# DrumMachine_Pic32_v1_2.net
KiCad netlist of a schematic drawn in EAGLE
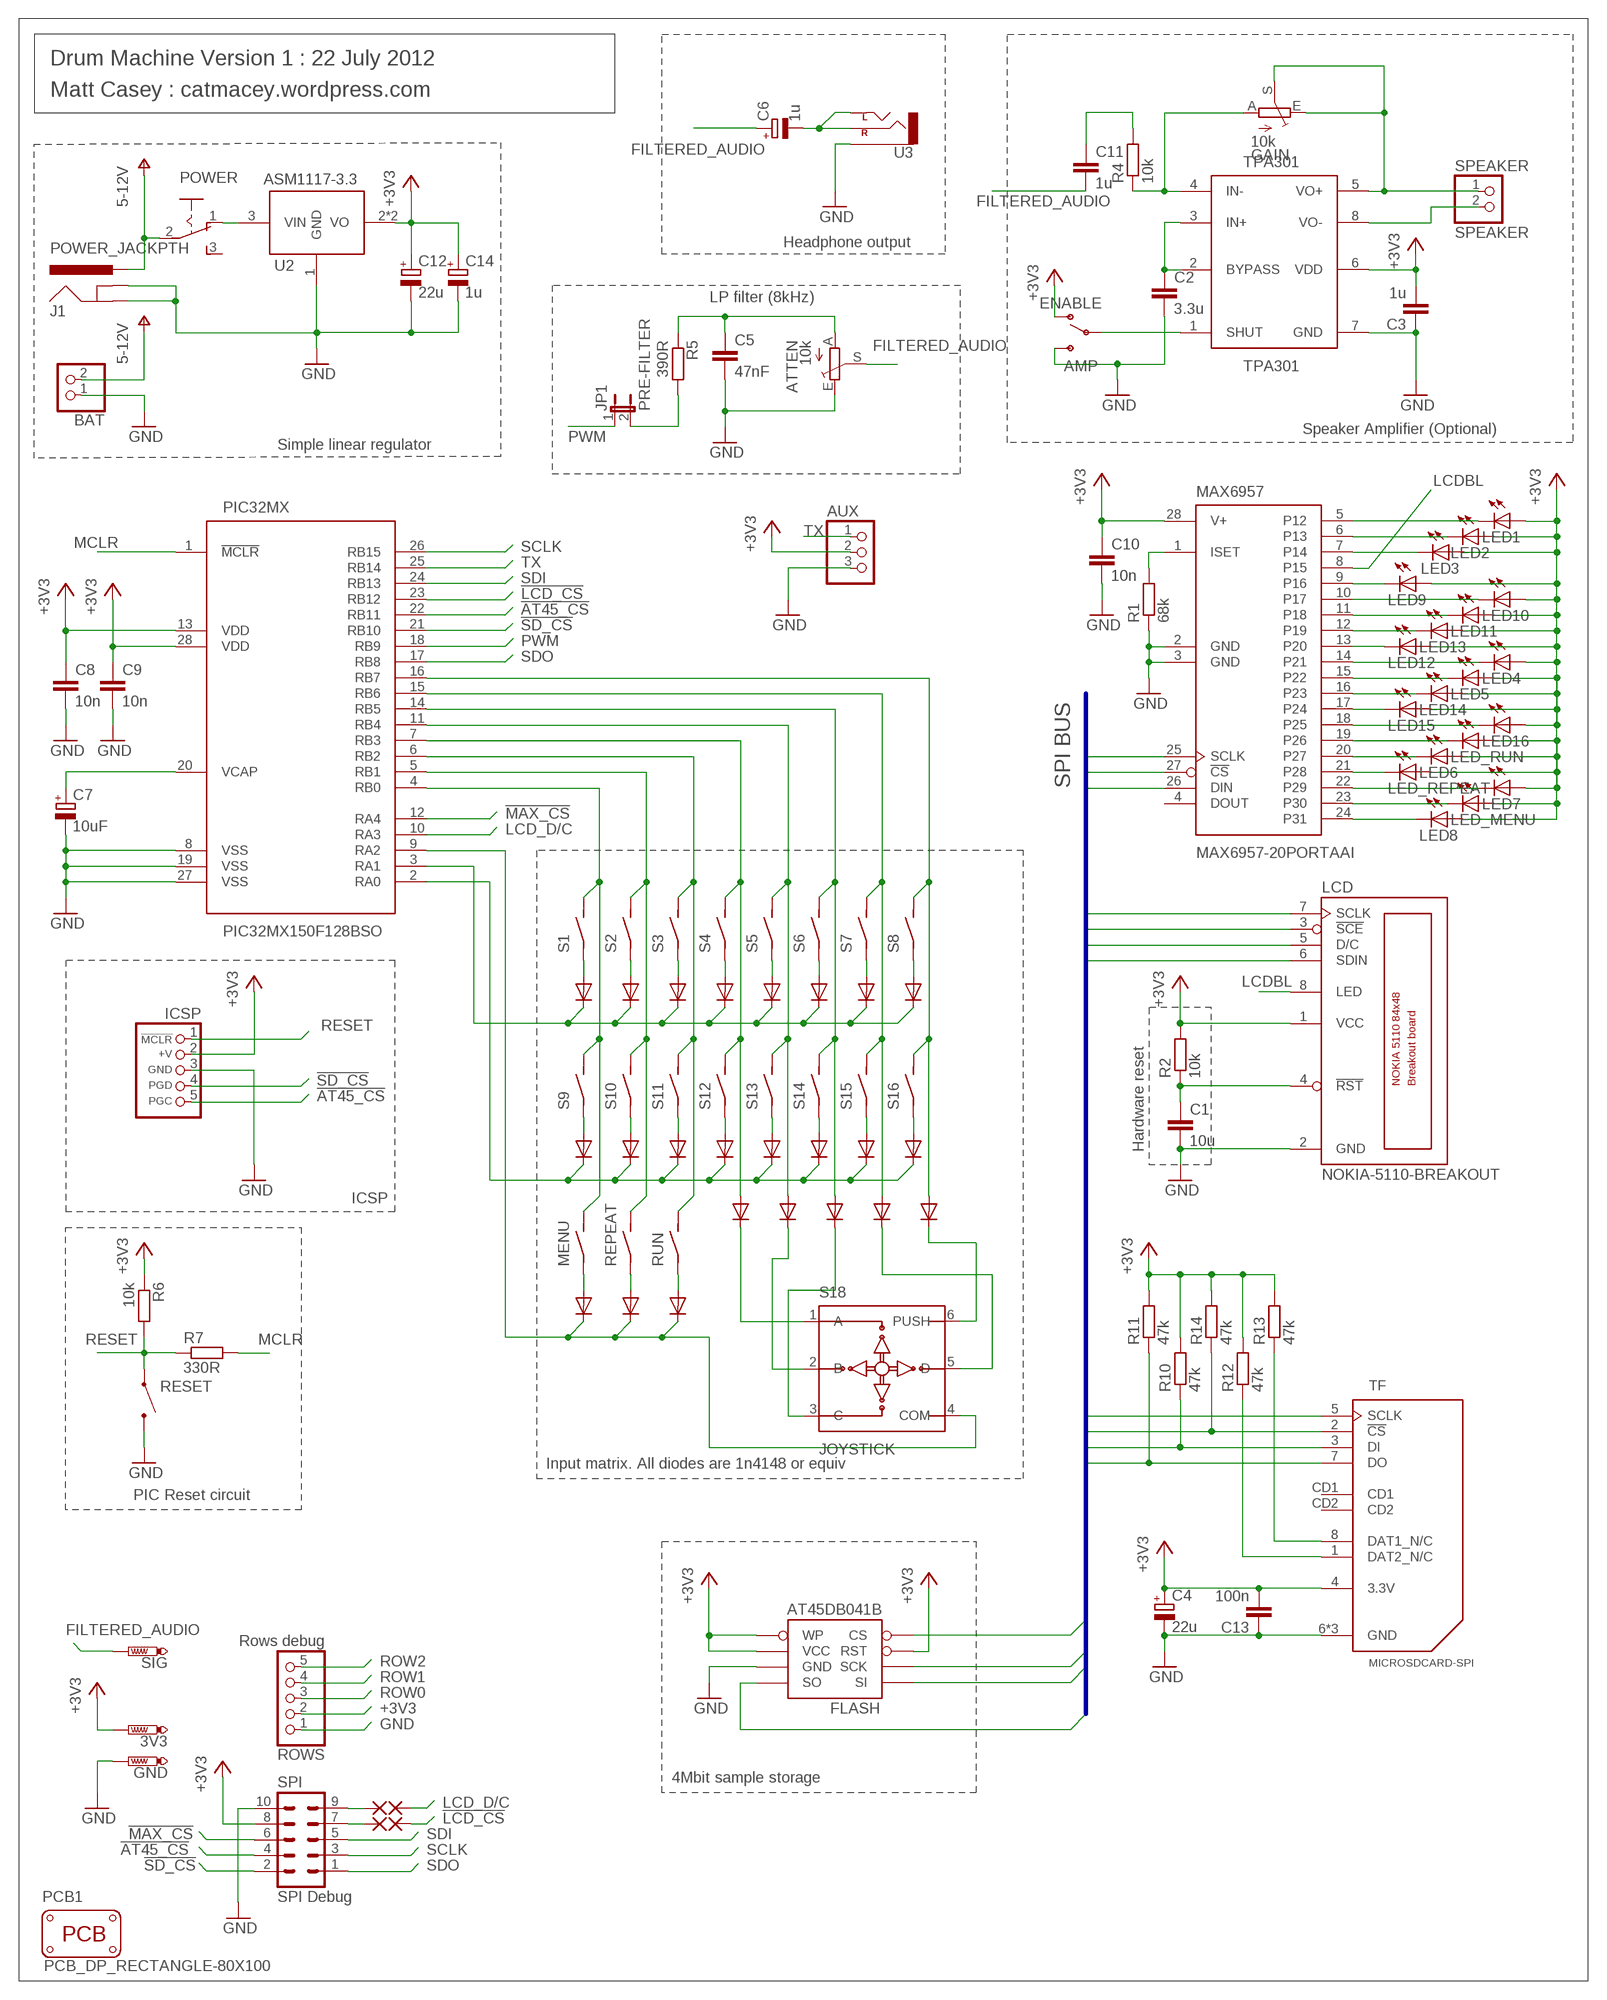
[diagram p0: schematic, sheet 1]

(export (version "E")
  (design (tool "Eeschema 10.0.6"))
  (components
    (comp (ref "3V3")
      (value "PTR1PAD1-13")
      (footprint "eagle-import:P1-13")
      (libsource (lib "eagle-import") (part "PTR1PAD1-13"))
    )
    (comp (ref "AMP")
      (value "ENABLE")
      (footprint "eagle-import:SWITCH-SPST-SMD-A")
      (libsource (lib "eagle-import") (part "SWITCH-SPST-SMD-A"))
    )
    (comp (ref "ATTEN")
      (value "10k")
      (footprint "eagle-import:CA6V")
      (libsource (lib "eagle-import") (part "TRIM_EU-CA6V"))
    )
    (comp (ref "AUX")
      (value "PINHD-1X3")
      (footprint "eagle-import:1X03")
      (libsource (lib "eagle-import") (part "PINHD-1X3"))
    )
    (comp (ref "BAT")
      (value "PINHD-1X2")
      (footprint "eagle-import:1X02")
      (libsource (lib "eagle-import") (part "PINHD-1X2"))
    )
    (comp (ref "C1")
      (value "10u")
      (footprint "eagle-import:C0805")
      (libsource (lib "eagle-import") (part "C-EUC0805"))
    )
    (comp (ref "C2")
      (value "3.3u")
      (footprint "eagle-import:C0805")
      (libsource (lib "eagle-import") (part "C-EUC0805"))
    )
    (comp (ref "C3")
      (value "1u")
      (footprint "eagle-import:C0805")
      (libsource (lib "eagle-import") (part "C-EUC0805"))
    )
    (comp (ref "C4")
      (value "22u")
      (footprint "eagle-import:SMC_A")
      (libsource (lib "eagle-import") (part "CPOL-EUSMCA"))
    )
    (comp (ref "C5")
      (value "47nF")
      (footprint "eagle-import:C0805")
      (libsource (lib "eagle-import") (part "C-EUC0805"))
    )
    (comp (ref "C6")
      (value "1u")
      (footprint "eagle-import:153CLV-0405")
      (libsource (lib "eagle-import") (part "CPOL-EU153CLV-0405"))
    )
    (comp (ref "C7")
      (value "10uF")
      (footprint "eagle-import:SMC_A")
      (libsource (lib "eagle-import") (part "CPOL-EUSMCA"))
    )
    (comp (ref "C8")
      (value "10n")
      (footprint "eagle-import:C0805")
      (libsource (lib "eagle-import") (part "resistor_C-EUC0805"))
    )
    (comp (ref "C9")
      (value "10n")
      (footprint "eagle-import:C0805")
      (libsource (lib "eagle-import") (part "resistor_C-EUC0805"))
    )
    (comp (ref "C10")
      (value "10n")
      (footprint "eagle-import:C0805")
      (libsource (lib "eagle-import") (part "resistor_C-EUC0805"))
    )
    (comp (ref "C11")
      (value "1u")
      (footprint "eagle-import:C0805")
      (libsource (lib "eagle-import") (part "C-EUC0805"))
    )
    (comp (ref "C12")
      (value "22u")
      (footprint "eagle-import:SMC_A")
      (libsource (lib "eagle-import") (part "CPOL-EUSMCA"))
    )
    (comp (ref "C13")
      (value "100n")
      (footprint "eagle-import:C0805")
      (libsource (lib "eagle-import") (part "resistor_C-EUC0805"))
    )
    (comp (ref "C14")
      (value "1u")
      (footprint "eagle-import:153CLV-0405")
      (libsource (lib "eagle-import") (part "CPOL-EU153CLV-0405"))
    )
    (comp (ref "D1")
      (value "DIODE-SOD-123")
      (footprint "eagle-import:SOD-123")
      (libsource (lib "eagle-import") (part "DIODE-SOD-123"))
    )
    (comp (ref "D2")
      (value "DIODE-SOD-123")
      (footprint "eagle-import:SOD-123")
      (libsource (lib "eagle-import") (part "DIODE-SOD-123"))
    )
    (comp (ref "D3")
      (value "DIODE-SOD-123")
      (footprint "eagle-import:SOD-123")
      (libsource (lib "eagle-import") (part "DIODE-SOD-123"))
    )
    (comp (ref "D4")
      (value "DIODE-SOD-123")
      (footprint "eagle-import:SOD-123")
      (libsource (lib "eagle-import") (part "DIODE-SOD-123"))
    )
    (comp (ref "D5")
      (value "DIODE-SOD-123")
      (footprint "eagle-import:SOD-123")
      (libsource (lib "eagle-import") (part "DIODE-SOD-123"))
    )
    (comp (ref "D6")
      (value "DIODE-SOD-123")
      (footprint "eagle-import:SOD-123")
      (libsource (lib "eagle-import") (part "DIODE-SOD-123"))
    )
    (comp (ref "D7")
      (value "DIODE-SOD-123")
      (footprint "eagle-import:SOD-123")
      (libsource (lib "eagle-import") (part "DIODE-SOD-123"))
    )
    (comp (ref "D8")
      (value "DIODE-SOD-123")
      (footprint "eagle-import:SOD-123")
      (libsource (lib "eagle-import") (part "DIODE-SOD-123"))
    )
    (comp (ref "D9")
      (value "DIODE-SOD-123")
      (footprint "eagle-import:SOD-123")
      (libsource (lib "eagle-import") (part "DIODE-SOD-123"))
    )
    (comp (ref "D10")
      (value "DIODE-SOD-123")
      (footprint "eagle-import:SOD-123")
      (libsource (lib "eagle-import") (part "DIODE-SOD-123"))
    )
    (comp (ref "D11")
      (value "DIODE-SOD-123")
      (footprint "eagle-import:SOD-123")
      (libsource (lib "eagle-import") (part "DIODE-SOD-123"))
    )
    (comp (ref "D12")
      (value "DIODE-SOD-123")
      (footprint "eagle-import:SOD-123")
      (libsource (lib "eagle-import") (part "DIODE-SOD-123"))
    )
    (comp (ref "D13")
      (value "DIODE-SOD-123")
      (footprint "eagle-import:SOD-123")
      (libsource (lib "eagle-import") (part "DIODE-SOD-123"))
    )
    (comp (ref "D14")
      (value "DIODE-SOD-123")
      (footprint "eagle-import:SOD-123")
      (libsource (lib "eagle-import") (part "DIODE-SOD-123"))
    )
    (comp (ref "D15")
      (value "DIODE-SOD-123")
      (footprint "eagle-import:SOD-123")
      (libsource (lib "eagle-import") (part "DIODE-SOD-123"))
    )
    (comp (ref "D16")
      (value "DIODE-SOD-123")
      (footprint "eagle-import:SOD-123")
      (libsource (lib "eagle-import") (part "DIODE-SOD-123"))
    )
    (comp (ref "D17")
      (value "DIODE-SOD-123")
      (footprint "eagle-import:SOD-123")
      (libsource (lib "eagle-import") (part "DIODE-SOD-123"))
    )
    (comp (ref "D18")
      (value "DIODE-SOD-123")
      (footprint "eagle-import:SOD-123")
      (libsource (lib "eagle-import") (part "DIODE-SOD-123"))
    )
    (comp (ref "D19")
      (value "DIODE-SOD-123")
      (footprint "eagle-import:SOD-123")
      (libsource (lib "eagle-import") (part "DIODE-SOD-123"))
    )
    (comp (ref "D20")
      (value "DIODE-SOD-123")
      (footprint "eagle-import:SOD-123")
      (libsource (lib "eagle-import") (part "DIODE-SOD-123"))
    )
    (comp (ref "D21")
      (value "DIODE-SOD-123")
      (footprint "eagle-import:SOD-123")
      (libsource (lib "eagle-import") (part "DIODE-SOD-123"))
    )
    (comp (ref "D22")
      (value "DIODE-SOD-123")
      (footprint "eagle-import:SOD-123")
      (libsource (lib "eagle-import") (part "DIODE-SOD-123"))
    )
    (comp (ref "D23")
      (value "DIODE-SOD-123")
      (footprint "eagle-import:SOD-123")
      (libsource (lib "eagle-import") (part "DIODE-SOD-123"))
    )
    (comp (ref "D25")
      (value "DIODE-SOD-123")
      (footprint "eagle-import:SOD-123")
      (libsource (lib "eagle-import") (part "DIODE-SOD-123"))
    )
    (comp (ref "FLASH")
      (value "AT45DB041B")
      (footprint "eagle-import:SO08")
      (libsource (lib "eagle-import") (part "AT45DB041B"))
    )
    (comp (ref "GAIN")
      (value "10k")
      (footprint "eagle-import:CA6V")
      (libsource (lib "eagle-import") (part "TRIM_EU-CA6V"))
    )
    (comp (ref "GND")
      (value "PTR1PAD1-13")
      (footprint "eagle-import:P1-13")
      (libsource (lib "eagle-import") (part "PTR1PAD1-13"))
    )
    (comp (ref "ICSP")
      (value "CON_HEADER_PRG_PIC_ICSPB")
      (footprint "eagle-import:HEADER_PRG_1X05_ICSP_B")
      (libsource (lib "eagle-import") (part "CON_HEADER_PRG_PIC_ICSPB"))
    )
    (comp (ref "J1")
      (value "POWER_JACKPTH")
      (footprint "eagle-import:POWER_JACK_PTH")
      (libsource (lib "eagle-import") (part "POWER_JACKPTH"))
    )
    (comp (ref "JP1")
      (value "PRE-FILTER")
      (footprint "eagle-import:JP1")
      (libsource (lib "eagle-import") (part "JP1E"))
    )
    (comp (ref "LCD")
      (value "NOKIA-5110-BREAKOUT")
      (footprint "eagle-import:NOKIA-5110-BREAKOUT")
      (libsource (lib "eagle-import") (part "NOKIA-5110-BREAKOUT"))
    )
    (comp (ref "LED1")
      (value "LEDCHIPLED_0805")
      (footprint "eagle-import:CHIPLED_0805")
      (libsource (lib "eagle-import") (part "LEDCHIPLED_0805"))
    )
    (comp (ref "LED2")
      (value "LEDCHIPLED_0805")
      (footprint "eagle-import:CHIPLED_0805")
      (libsource (lib "eagle-import") (part "LEDCHIPLED_0805"))
    )
    (comp (ref "LED3")
      (value "LEDCHIPLED_0805")
      (footprint "eagle-import:CHIPLED_0805")
      (libsource (lib "eagle-import") (part "LEDCHIPLED_0805"))
    )
    (comp (ref "LED4")
      (value "LEDCHIPLED_0805")
      (footprint "eagle-import:CHIPLED_0805")
      (libsource (lib "eagle-import") (part "LEDCHIPLED_0805"))
    )
    (comp (ref "LED5")
      (value "LEDCHIPLED_0805")
      (footprint "eagle-import:CHIPLED_0805")
      (libsource (lib "eagle-import") (part "LEDCHIPLED_0805"))
    )
    (comp (ref "LED6")
      (value "LEDCHIPLED_0805")
      (footprint "eagle-import:CHIPLED_0805")
      (libsource (lib "eagle-import") (part "LEDCHIPLED_0805"))
    )
    (comp (ref "LED7")
      (value "LEDCHIPLED_0805")
      (footprint "eagle-import:CHIPLED_0805")
      (libsource (lib "eagle-import") (part "LEDCHIPLED_0805"))
    )
    (comp (ref "LED8")
      (value "LEDCHIPLED_0805")
      (footprint "eagle-import:CHIPLED_0805")
      (libsource (lib "eagle-import") (part "LEDCHIPLED_0805"))
    )
    (comp (ref "LED9")
      (value "LEDCHIPLED_0805")
      (footprint "eagle-import:CHIPLED_0805")
      (libsource (lib "eagle-import") (part "LEDCHIPLED_0805"))
    )
    (comp (ref "LED10")
      (value "LEDCHIPLED_0805")
      (footprint "eagle-import:CHIPLED_0805")
      (libsource (lib "eagle-import") (part "LEDCHIPLED_0805"))
    )
    (comp (ref "LED11")
      (value "LEDCHIPLED_0805")
      (footprint "eagle-import:CHIPLED_0805")
      (libsource (lib "eagle-import") (part "LEDCHIPLED_0805"))
    )
    (comp (ref "LED12")
      (value "LEDCHIPLED_0805")
      (footprint "eagle-import:CHIPLED_0805")
      (libsource (lib "eagle-import") (part "LEDCHIPLED_0805"))
    )
    (comp (ref "LED13")
      (value "LEDCHIPLED_0805")
      (footprint "eagle-import:CHIPLED_0805")
      (libsource (lib "eagle-import") (part "LEDCHIPLED_0805"))
    )
    (comp (ref "LED14")
      (value "LEDCHIPLED_0805")
      (footprint "eagle-import:CHIPLED_0805")
      (libsource (lib "eagle-import") (part "LEDCHIPLED_0805"))
    )
    (comp (ref "LED15")
      (value "LEDCHIPLED_0805")
      (footprint "eagle-import:CHIPLED_0805")
      (libsource (lib "eagle-import") (part "LEDCHIPLED_0805"))
    )
    (comp (ref "LED16")
      (value "LEDCHIPLED_0805")
      (footprint "eagle-import:CHIPLED_0805")
      (libsource (lib "eagle-import") (part "LEDCHIPLED_0805"))
    )
    (comp (ref "LED_MENU")
      (value "LEDCHIPLED_0805")
      (footprint "eagle-import:CHIPLED_0805")
      (libsource (lib "eagle-import") (part "LEDCHIPLED_0805"))
    )
    (comp (ref "LED_REPEAT")
      (value "LEDCHIPLED_0805")
      (footprint "eagle-import:CHIPLED_0805")
      (libsource (lib "eagle-import") (part "LEDCHIPLED_0805"))
    )
    (comp (ref "LED_RUN")
      (value "LEDCHIPLED_0805")
      (footprint "eagle-import:CHIPLED_0805")
      (libsource (lib "eagle-import") (part "LEDCHIPLED_0805"))
    )
    (comp (ref "MAX6957")
      (value "MAX6957-20PORTAAI")
      (footprint "eagle-import:SSOP28")
      (libsource (lib "eagle-import") (part "MAX6957-20PORTAAI"))
    )
    (comp (ref "MENU")
      (value "ITT-PTS645SMD")
      (footprint "eagle-import:ITT-PTS645SMD")
      (libsource (lib "eagle-import") (part "ITT-PTS645SMD"))
    )
    (comp (ref "P1")
      (value "DEBUG_LCD_CS")
      (footprint "eagle-import:1,2_0,5")
      (libsource (lib "eagle-import") (part "1,6/0,81.2/0.5"))
    )
    (comp (ref "P1A")
      (value "LCD CS")
      (footprint "eagle-import:1,2_0,5")
      (libsource (lib "eagle-import") (part "1,6/0,81.2/0.5"))
    )
    (comp (ref "P2")
      (value "DEBUG_LCD_D/c")
      (footprint "eagle-import:1,2_0,5")
      (libsource (lib "eagle-import") (part "1,6/0,81.2/0.5"))
    )
    (comp (ref "P2A")
      (value "1,6/0,81.2/0.5")
      (footprint "eagle-import:1,2_0,5")
      (libsource (lib "eagle-import") (part "1,6/0,81.2/0.5"))
    )
    (comp (ref "PCB1")
      (value "PCB_DP_RECTANGLE-80X100")
      (footprint "eagle-import:DP10080_V1")
      (libsource (lib "eagle-import") (part "PCB_DP_RECTANGLE-80X100"))
    )
    (comp (ref "PIC32MX")
      (value "PIC32MX150F128BSO")
      (footprint "eagle-import:SO-28")
      (libsource (lib "eagle-import") (part "PIC32MX150F128BSO"))
    )
    (comp (ref "POWER")
      (value "DX_MINI_SPDT")
      (footprint "eagle-import:DX_MINI_SPDT_VERTICAL")
      (libsource (lib "eagle-import") (part "DX_MINI_SPDT"))
    )
    (comp (ref "R1")
      (value "68k")
      (footprint "eagle-import:R0805")
      (libsource (lib "eagle-import") (part "R-EU_R0805"))
    )
    (comp (ref "R2")
      (value "10k")
      (footprint "eagle-import:R0805")
      (libsource (lib "eagle-import") (part "R-EU_R0805"))
    )
    (comp (ref "R4")
      (value "10k")
      (footprint "eagle-import:R0805")
      (libsource (lib "eagle-import") (part "R-EU_R0805"))
    )
    (comp (ref "R5")
      (value "390R")
      (footprint "eagle-import:R0805")
      (libsource (lib "eagle-import") (part "R-EU_R0805"))
    )
    (comp (ref "R6")
      (value "10k")
      (footprint "eagle-import:R0805")
      (libsource (lib "eagle-import") (part "R-EU_R0805"))
    )
    (comp (ref "R7")
      (value "330R")
      (footprint "eagle-import:R0805")
      (libsource (lib "eagle-import") (part "R-EU_R0805"))
    )
    (comp (ref "R10")
      (value "47k")
      (footprint "eagle-import:R0805")
      (libsource (lib "eagle-import") (part "R-EU_R0805"))
    )
    (comp (ref "R11")
      (value "47k")
      (footprint "eagle-import:R0805")
      (libsource (lib "eagle-import") (part "R-EU_R0805"))
    )
    (comp (ref "R12")
      (value "47k")
      (footprint "eagle-import:R0805")
      (libsource (lib "eagle-import") (part "R-EU_R0805"))
    )
    (comp (ref "R13")
      (value "47k")
      (footprint "eagle-import:R0805")
      (libsource (lib "eagle-import") (part "R-EU_R0805"))
    )
    (comp (ref "R14")
      (value "47k")
      (footprint "eagle-import:R0805")
      (libsource (lib "eagle-import") (part "R-EU_R0805"))
    )
    (comp (ref "REPEAT")
      (value "ITT-PTS645SMD")
      (footprint "eagle-import:ITT-PTS645SMD")
      (libsource (lib "eagle-import") (part "ITT-PTS645SMD"))
    )
    (comp (ref "RESET")
      (value "TINY_TACTILESMD")
      (footprint "eagle-import:TINY_TACTILE_SMD")
      (libsource (lib "eagle-import") (part "TINY_TACTILESMD"))
    )
    (comp (ref "ROWS")
      (value "Rows debug")
      (footprint "eagle-import:1X05")
      (libsource (lib "eagle-import") (part "PINHD-1X5"))
    )
    (comp (ref "RUN")
      (value "ITT-PTS645SMD")
      (footprint "eagle-import:ITT-PTS645SMD")
      (libsource (lib "eagle-import") (part "ITT-PTS645SMD"))
    )
    (comp (ref "S1")
      (value "ITT-PTS645SMD")
      (footprint "eagle-import:ITT-PTS645SMD")
      (libsource (lib "eagle-import") (part "ITT-PTS645SMD"))
    )
    (comp (ref "S2")
      (value "ITT-PTS645SMD")
      (footprint "eagle-import:ITT-PTS645SMD")
      (libsource (lib "eagle-import") (part "ITT-PTS645SMD"))
    )
    (comp (ref "S3")
      (value "ITT-PTS645SMD")
      (footprint "eagle-import:ITT-PTS645SMD")
      (libsource (lib "eagle-import") (part "ITT-PTS645SMD"))
    )
    (comp (ref "S4")
      (value "ITT-PTS645SMD")
      (footprint "eagle-import:ITT-PTS645SMD")
      (libsource (lib "eagle-import") (part "ITT-PTS645SMD"))
    )
    (comp (ref "S5")
      (value "ITT-PTS645SMD")
      (footprint "eagle-import:ITT-PTS645SMD")
      (libsource (lib "eagle-import") (part "ITT-PTS645SMD"))
    )
    (comp (ref "S6")
      (value "ITT-PTS645SMD")
      (footprint "eagle-import:ITT-PTS645SMD")
      (libsource (lib "eagle-import") (part "ITT-PTS645SMD"))
    )
    (comp (ref "S7")
      (value "ITT-PTS645SMD")
      (footprint "eagle-import:ITT-PTS645SMD")
      (libsource (lib "eagle-import") (part "ITT-PTS645SMD"))
    )
    (comp (ref "S8")
      (value "ITT-PTS645SMD")
      (footprint "eagle-import:ITT-PTS645SMD")
      (libsource (lib "eagle-import") (part "ITT-PTS645SMD"))
    )
    (comp (ref "S9")
      (value "ITT-PTS645SMD")
      (footprint "eagle-import:ITT-PTS645SMD")
      (libsource (lib "eagle-import") (part "ITT-PTS645SMD"))
    )
    (comp (ref "S10")
      (value "ITT-PTS645SMD")
      (footprint "eagle-import:ITT-PTS645SMD")
      (libsource (lib "eagle-import") (part "ITT-PTS645SMD"))
    )
    (comp (ref "S11")
      (value "ITT-PTS645SMD")
      (footprint "eagle-import:ITT-PTS645SMD")
      (libsource (lib "eagle-import") (part "ITT-PTS645SMD"))
    )
    (comp (ref "S12")
      (value "ITT-PTS645SMD")
      (footprint "eagle-import:ITT-PTS645SMD")
      (libsource (lib "eagle-import") (part "ITT-PTS645SMD"))
    )
    (comp (ref "S13")
      (value "ITT-PTS645SMD")
      (footprint "eagle-import:ITT-PTS645SMD")
      (libsource (lib "eagle-import") (part "ITT-PTS645SMD"))
    )
    (comp (ref "S14")
      (value "ITT-PTS645SMD")
      (footprint "eagle-import:ITT-PTS645SMD")
      (libsource (lib "eagle-import") (part "ITT-PTS645SMD"))
    )
    (comp (ref "S15")
      (value "ITT-PTS645SMD")
      (footprint "eagle-import:ITT-PTS645SMD")
      (libsource (lib "eagle-import") (part "ITT-PTS645SMD"))
    )
    (comp (ref "S16")
      (value "ITT-PTS645SMD")
      (footprint "eagle-import:ITT-PTS645SMD")
      (libsource (lib "eagle-import") (part "ITT-PTS645SMD"))
    )
    (comp (ref "S18")
      (value "JOYSTICK")
      (footprint "eagle-import:ALPS_SKQU_JOYSTICK")
      (libsource (lib "eagle-import") (part "ALPS_SKQU_JOYSTICK"))
    )
    (comp (ref "SIG")
      (value "PTR1PAD1-13")
      (footprint "eagle-import:P1-13")
      (libsource (lib "eagle-import") (part "PTR1PAD1-13"))
    )
    (comp (ref "SPEAKER")
      (value "SPEAKER")
      (footprint "eagle-import:1X02")
      (libsource (lib "eagle-import") (part "PINHD-1X2"))
    )
    (comp (ref "SPI")
      (value "SPI Debug")
      (footprint "eagle-import:MA05-2")
      (libsource (lib "eagle-import") (part "MA05-2"))
    )
    (comp (ref "TF")
      (value "MICROSDCARD-SPI")
      (footprint "eagle-import:TCF001_MICROSD_SOCKET")
      (libsource (lib "eagle-import") (part "MICROSDCARD-SPI"))
    )
    (comp (ref "TPA301")
      (value "TPA301")
      (footprint "eagle-import:SO-08")
      (libsource (lib "eagle-import") (part "TPA301"))
    )
    (comp (ref "U2")
      (value "ASM1117-3.3")
      (footprint "eagle-import:SOT223")
      (libsource (lib "eagle-import") (part "ASM1117-3.3"))
    )
    (comp (ref "U3")
      (value "AUDIO-JACKPTH")
      (footprint "eagle-import:STEREO_JACK3.5MM_PTH")
      (libsource (lib "eagle-import") (part "AUDIO-JACKPTH"))
    )
  )
  (nets
    (net (code "1") (name "+3V3") (class "Default")
      (node (ref "3V3") (pin "TP") (pinfunction "TP_TP") (pintype "input"))
      (node (ref "AMP") (pin "1") (pinfunction "O_1") (pintype "passive"))
      (node (ref "AUX") (pin "2") (pinfunction "2_2") (pintype "passive"))
      (node (ref "C10") (pin "1") (pinfunction "1_1") (pintype "passive"))
      (node (ref "C12") (pin "+") (pinfunction "+_+") (pintype "passive"))
      (node (ref "C13") (pin "2") (pinfunction "2_2") (pintype "passive"))
      (node (ref "C14") (pin "+") (pinfunction "+_+") (pintype "passive"))
      (node (ref "C3") (pin "2") (pinfunction "2_2") (pintype "passive"))
      (node (ref "C4") (pin "+") (pinfunction "+_+") (pintype "passive"))
      (node (ref "C8") (pin "1") (pinfunction "1_1") (pintype "passive"))
      (node (ref "C9") (pin "1") (pinfunction "1_1") (pintype "passive"))
      (node (ref "FLASH") (pin "3") (pinfunction "RST_3") (pintype "bidirectional"))
      (node (ref "FLASH") (pin "5") (pinfunction "WP_5") (pintype "bidirectional"))
      (node (ref "FLASH") (pin "6") (pinfunction "VCC_6") (pintype "bidirectional"))
      (node (ref "ICSP") (pin "2") (pinfunction "+V_2") (pintype "passive"))
      (node (ref "LCD") (pin "1") (pinfunction "VCC_1") (pintype "power_in"))
      (node (ref "LED1") (pin "A") (pinfunction "A_A") (pintype "passive"))
      (node (ref "LED10") (pin "A") (pinfunction "A_A") (pintype "passive"))
      (node (ref "LED11") (pin "A") (pinfunction "A_A") (pintype "passive"))
      (node (ref "LED12") (pin "A") (pinfunction "A_A") (pintype "passive"))
      (node (ref "LED13") (pin "A") (pinfunction "A_A") (pintype "passive"))
      (node (ref "LED14") (pin "A") (pinfunction "A_A") (pintype "passive"))
      (node (ref "LED15") (pin "A") (pinfunction "A_A") (pintype "passive"))
      (node (ref "LED16") (pin "A") (pinfunction "A_A") (pintype "passive"))
      (node (ref "LED2") (pin "A") (pinfunction "A_A") (pintype "passive"))
      (node (ref "LED3") (pin "A") (pinfunction "A_A") (pintype "passive"))
      (node (ref "LED4") (pin "A") (pinfunction "A_A") (pintype "passive"))
      (node (ref "LED5") (pin "A") (pinfunction "A_A") (pintype "passive"))
      (node (ref "LED6") (pin "A") (pinfunction "A_A") (pintype "passive"))
      (node (ref "LED7") (pin "A") (pinfunction "A_A") (pintype "passive"))
      (node (ref "LED8") (pin "A") (pinfunction "A_A") (pintype "passive"))
      (node (ref "LED9") (pin "A") (pinfunction "A_A") (pintype "passive"))
      (node (ref "LED_MENU") (pin "A") (pinfunction "A_A") (pintype "passive"))
      (node (ref "LED_REPEAT") (pin "A") (pinfunction "A_A") (pintype "passive"))
      (node (ref "LED_RUN") (pin "A") (pinfunction "A_A") (pintype "passive"))
      (node (ref "MAX6957") (pin "28") (pinfunction "V+_28") (pintype "power_in"))
      (node (ref "PIC32MX") (pin "13") (pinfunction "VDD_13") (pintype "power_in"))
      (node (ref "PIC32MX") (pin "28") (pinfunction "VDD_28") (pintype "power_in"))
      (node (ref "R10") (pin "2") (pinfunction "2_2") (pintype "passive"))
      (node (ref "R11") (pin "2") (pinfunction "2_2") (pintype "passive"))
      (node (ref "R12") (pin "2") (pinfunction "2_2") (pintype "passive"))
      (node (ref "R13") (pin "2") (pinfunction "2_2") (pintype "passive"))
      (node (ref "R14") (pin "2") (pinfunction "2_2") (pintype "passive"))
      (node (ref "R2") (pin "2") (pinfunction "2_2") (pintype "passive"))
      (node (ref "R6") (pin "1") (pinfunction "1_1") (pintype "passive"))
      (node (ref "ROWS") (pin "2") (pinfunction "2_2") (pintype "passive"))
      (node (ref "SPI") (pin "8") (pinfunction "8_8") (pintype "passive"))
      (node (ref "TF") (pin "4") (pinfunction "3.3V_4") (pintype "power_in"))
      (node (ref "TPA301") (pin "6") (pinfunction "VDD_6") (pintype "power_in"))
      (node (ref "U2") (pin "2") (pinfunction "VO_2") (pintype "bidirectional"))
      (node (ref "U2") (pin "4") (pinfunction "VO_4") (pintype "bidirectional"))
    )
    (net (code "2") (name "/FILTERED_AUDIO") (class "Default")
      (node (ref "ATTEN") (pin "S") (pinfunction "S_S") (pintype "passive"))
      (node (ref "C11") (pin "2") (pinfunction "2_2") (pintype "passive"))
      (node (ref "C6") (pin "+") (pinfunction "+_+") (pintype "passive"))
      (node (ref "SIG") (pin "TP") (pinfunction "TP_TP") (pintype "input"))
    )
    (net (code "3") (name "/LCDBL") (class "Default")
      (node (ref "LCD") (pin "8") (pinfunction "LED_8") (pintype "passive"))
      (node (ref "MAX6957") (pin "8") (pinfunction "P15_8") (pintype "bidirectional"))
    )
    (net (code "4") (name "/LCD_D{slash}C") (class "Default")
      (node (ref "LCD") (pin "5") (pinfunction "D/C_5") (pintype "input"))
      (node (ref "P2") (pin "1") (pinfunction "P_1") (pintype "passive"))
      (node (ref "P2A") (pin "1") (pinfunction "P_1") (pintype "passive"))
      (node (ref "PIC32MX") (pin "10") (pinfunction "RA3_10") (pintype "bidirectional"))
      (node (ref "SPI") (pin "9") (pinfunction "9_9") (pintype "passive"))
    )
    (net (code "5") (name "/MCLR") (class "Default")
      (node (ref "PIC32MX") (pin "1") (pinfunction "~{MCLR}_1") (pintype "input"))
      (node (ref "R7") (pin "2") (pinfunction "2_2") (pintype "passive"))
    )
    (net (code "6") (name "/PWM") (class "Default")
      (node (ref "JP1") (pin "1") (pinfunction "1_1") (pintype "passive"))
      (node (ref "PIC32MX") (pin "18") (pinfunction "RB9_18") (pintype "bidirectional"))
    )
    (net (code "7") (name "/RESET") (class "Default")
      (node (ref "ICSP") (pin "1") (pinfunction "/MCLR_1") (pintype "passive"))
      (node (ref "R6") (pin "2") (pinfunction "2_2") (pintype "passive"))
      (node (ref "R7") (pin "1") (pinfunction "1_1") (pintype "passive"))
      (node (ref "RESET") (pin "1") (pinfunction "A_1") (pintype "passive"))
    )
    (net (code "8") (name "/ROW0") (class "Default")
      (node (ref "D1") (pin "C") (pinfunction "C_C") (pintype "passive"))
      (node (ref "D2") (pin "C") (pinfunction "C_C") (pintype "passive"))
      (node (ref "D25") (pin "C") (pinfunction "C_C") (pintype "passive"))
      (node (ref "D3") (pin "C") (pinfunction "C_C") (pintype "passive"))
      (node (ref "D4") (pin "C") (pinfunction "C_C") (pintype "passive"))
      (node (ref "D5") (pin "C") (pinfunction "C_C") (pintype "passive"))
      (node (ref "D6") (pin "C") (pinfunction "C_C") (pintype "passive"))
      (node (ref "D7") (pin "C") (pinfunction "C_C") (pintype "passive"))
      (node (ref "PIC32MX") (pin "3") (pinfunction "RA1_3") (pintype "bidirectional"))
      (node (ref "ROWS") (pin "3") (pinfunction "3_3") (pintype "passive"))
    )
    (net (code "9") (name "/ROW1") (class "Default")
      (node (ref "D10") (pin "C") (pinfunction "C_C") (pintype "passive"))
      (node (ref "D11") (pin "C") (pinfunction "C_C") (pintype "passive"))
      (node (ref "D12") (pin "C") (pinfunction "C_C") (pintype "passive"))
      (node (ref "D13") (pin "C") (pinfunction "C_C") (pintype "passive"))
      (node (ref "D14") (pin "C") (pinfunction "C_C") (pintype "passive"))
      (node (ref "D15") (pin "C") (pinfunction "C_C") (pintype "passive"))
      (node (ref "D8") (pin "C") (pinfunction "C_C") (pintype "passive"))
      (node (ref "D9") (pin "C") (pinfunction "C_C") (pintype "passive"))
      (node (ref "PIC32MX") (pin "2") (pinfunction "RA0_2") (pintype "bidirectional"))
      (node (ref "ROWS") (pin "4") (pinfunction "4_4") (pintype "passive"))
    )
    (net (code "10") (name "/ROW2") (class "Default")
      (node (ref "D16") (pin "C") (pinfunction "C_C") (pintype "passive"))
      (node (ref "D17") (pin "C") (pinfunction "C_C") (pintype "passive"))
      (node (ref "D18") (pin "C") (pinfunction "C_C") (pintype "passive"))
      (node (ref "PIC32MX") (pin "9") (pinfunction "RA2_9") (pintype "bidirectional"))
      (node (ref "ROWS") (pin "5") (pinfunction "5_5") (pintype "passive"))
      (node (ref "S18") (pin "4") (pinfunction "COM_4") (pintype "passive"))
    )
    (net (code "11") (name "/SCLK") (class "Default")
      (node (ref "FLASH") (pin "2") (pinfunction "SCK_2") (pintype "bidirectional"))
      (node (ref "LCD") (pin "7") (pinfunction "SCLK_7") (pintype "input"))
      (node (ref "MAX6957") (pin "25") (pinfunction "SCLK_25") (pintype "bidirectional"))
      (node (ref "PIC32MX") (pin "26") (pinfunction "RB15_26") (pintype "bidirectional"))
      (node (ref "SPI") (pin "3") (pinfunction "3_3") (pintype "passive"))
      (node (ref "TF") (pin "5") (pinfunction "SCLK_5") (pintype "input"))
    )
    (net (code "12") (name "/SDI") (class "Default")
      (node (ref "FLASH") (pin "8") (pinfunction "SO_8") (pintype "bidirectional"))
      (node (ref "PIC32MX") (pin "24") (pinfunction "RB13_24") (pintype "bidirectional"))
      (node (ref "R11") (pin "1") (pinfunction "1_1") (pintype "passive"))
      (node (ref "SPI") (pin "5") (pinfunction "5_5") (pintype "passive"))
      (node (ref "TF") (pin "7") (pinfunction "DO_7") (pintype "output"))
    )
    (net (code "13") (name "/SDO") (class "Default")
      (node (ref "FLASH") (pin "1") (pinfunction "SI_1") (pintype "bidirectional"))
      (node (ref "LCD") (pin "6") (pinfunction "SDIN_6") (pintype "input"))
      (node (ref "MAX6957") (pin "26") (pinfunction "DIN_26") (pintype "bidirectional"))
      (node (ref "PIC32MX") (pin "17") (pinfunction "RB8_17") (pintype "input"))
      (node (ref "R10") (pin "1") (pinfunction "1_1") (pintype "passive"))
      (node (ref "SPI") (pin "1") (pinfunction "1_1") (pintype "passive"))
      (node (ref "TF") (pin "3") (pinfunction "DI_3") (pintype "input"))
    )
    (net (code "14") (name "/TX") (class "Default")
      (node (ref "AUX") (pin "1") (pinfunction "1_1") (pintype "passive"))
      (node (ref "PIC32MX") (pin "25") (pinfunction "RB14_25") (pintype "bidirectional"))
    )
    (net (code "15") (name "/~{AT45_CS}") (class "Default")
      (node (ref "FLASH") (pin "4") (pinfunction "CS_4") (pintype "bidirectional"))
      (node (ref "ICSP") (pin "5") (pinfunction "PGC_5") (pintype "passive"))
      (node (ref "PIC32MX") (pin "22") (pinfunction "RB11_22") (pintype "bidirectional"))
      (node (ref "SPI") (pin "4") (pinfunction "4_4") (pintype "passive"))
    )
    (net (code "16") (name "/~{LCD_CS}") (class "Default")
      (node (ref "LCD") (pin "3") (pinfunction "~{SCE}_3") (pintype "input"))
      (node (ref "P1") (pin "1") (pinfunction "P_1") (pintype "passive"))
      (node (ref "P1A") (pin "1") (pinfunction "P_1") (pintype "passive"))
      (node (ref "PIC32MX") (pin "23") (pinfunction "RB12_23") (pintype "bidirectional"))
      (node (ref "SPI") (pin "7") (pinfunction "7_7") (pintype "passive"))
    )
    (net (code "17") (name "/~{MAX_CS}") (class "Default")
      (node (ref "MAX6957") (pin "27") (pinfunction "~{CS}_27") (pintype "bidirectional"))
      (node (ref "PIC32MX") (pin "12") (pinfunction "RA4_12") (pintype "bidirectional"))
      (node (ref "SPI") (pin "6") (pinfunction "6_6") (pintype "passive"))
    )
    (net (code "18") (name "/~{SD_CS}") (class "Default")
      (node (ref "ICSP") (pin "4") (pinfunction "PGD_4") (pintype "passive"))
      (node (ref "PIC32MX") (pin "21") (pinfunction "RB10_21") (pintype "bidirectional"))
      (node (ref "R14") (pin "1") (pinfunction "1_1") (pintype "passive"))
      (node (ref "SPI") (pin "2") (pinfunction "2_2") (pintype "passive"))
      (node (ref "TF") (pin "2") (pinfunction "~{CS}_2") (pintype "input"))
    )
    (net (code "19") (name "5-12V") (class "Default")
      (node (ref "BAT") (pin "2") (pinfunction "2_2") (pintype "passive"))
      (node (ref "J1") (pin "PWR") (pinfunction "PWR_PWR") (pintype "bidirectional"))
      (node (ref "POWER") (pin "2") (pinfunction "P_2") (pintype "passive"))
    )
    (net (code "20") (name "GND") (class "Default")
      (node (ref "AMP") (pin "3") (pinfunction "S_3") (pintype "passive"))
      (node (ref "ATTEN") (pin "E") (pinfunction "E_E") (pintype "passive"))
      (node (ref "AUX") (pin "3") (pinfunction "3_3") (pintype "passive"))
      (node (ref "BAT") (pin "1") (pinfunction "1_1") (pintype "passive"))
      (node (ref "C1") (pin "2") (pinfunction "2_2") (pintype "passive"))
      (node (ref "C10") (pin "2") (pinfunction "2_2") (pintype "passive"))
      (node (ref "C12") (pin "-") (pinfunction "-_-") (pintype "passive"))
      (node (ref "C13") (pin "1") (pinfunction "1_1") (pintype "passive"))
      (node (ref "C14") (pin "-") (pinfunction "-_-") (pintype "passive"))
      (node (ref "C2") (pin "2") (pinfunction "2_2") (pintype "passive"))
      (node (ref "C3") (pin "1") (pinfunction "1_1") (pintype "passive"))
      (node (ref "C4") (pin "-") (pinfunction "-_-") (pintype "passive"))
      (node (ref "C5") (pin "2") (pinfunction "2_2") (pintype "passive"))
      (node (ref "C7") (pin "-") (pinfunction "-_-") (pintype "passive"))
      (node (ref "C8") (pin "2") (pinfunction "2_2") (pintype "passive"))
      (node (ref "C9") (pin "2") (pinfunction "2_2") (pintype "passive"))
      (node (ref "FLASH") (pin "7") (pinfunction "GND_7") (pintype "bidirectional"))
      (node (ref "GND") (pin "TP") (pinfunction "TP_TP") (pintype "input"))
      (node (ref "ICSP") (pin "3") (pinfunction "GND_3") (pintype "passive"))
      (node (ref "J1") (pin "GND") (pinfunction "GND_GND") (pintype "bidirectional"))
      (node (ref "J1") (pin "GNDBREAK") (pinfunction "GNDBREAK_GNDBREAK") (pintype "bidirectional"))
      (node (ref "LCD") (pin "2") (pinfunction "GND_2") (pintype "power_in"))
      (node (ref "MAX6957") (pin "2") (pinfunction "GND_2") (pintype "power_in"))
      (node (ref "MAX6957") (pin "3") (pinfunction "GND_3") (pintype "power_in"))
      (node (ref "PIC32MX") (pin "19") (pinfunction "VSS_19") (pintype "power_in"))
      (node (ref "PIC32MX") (pin "27") (pinfunction "VSS_27") (pintype "power_in"))
      (node (ref "PIC32MX") (pin "8") (pinfunction "VSS_8") (pintype "power_in"))
      (node (ref "R1") (pin "1") (pinfunction "1_1") (pintype "passive"))
      (node (ref "RESET") (pin "2") (pinfunction "B_2") (pintype "passive"))
      (node (ref "ROWS") (pin "1") (pinfunction "1_1") (pintype "passive"))
      (node (ref "SPI") (pin "10") (pinfunction "10_10") (pintype "passive"))
      (node (ref "TF") (pin "6") (pinfunction "GND_6") (pintype "power_in"))
      (node (ref "TF") (pin "P$11") (pinfunction "GND_P$11") (pintype "power_in"))
      (node (ref "TF") (pin "P$12") (pinfunction "GND_P$12") (pintype "power_in"))
      (node (ref "TPA301") (pin "7") (pinfunction "GND_7") (pintype "power_in"))
      (node (ref "U2") (pin "1") (pinfunction "GND_1") (pintype "bidirectional"))
      (node (ref "U3") (pin "S") (pinfunction "SLEEVE_S") (pintype "bidirectional"))
      (node (ref "U3") (pin "S@1") (pinfunction "SLEEVE_S@1") (pintype "bidirectional"))
    )
    (net (code "21") (name "Net-(AMP-P)") (class "Default")
      (node (ref "AMP") (pin "2") (pinfunction "P_2") (pintype "passive"))
      (node (ref "TPA301") (pin "1") (pinfunction "SHUT_1") (pintype "input"))
    )
    (net (code "22") (name "Net-(ATTEN-PadA)") (class "Default")
      (node (ref "ATTEN") (pin "A") (pinfunction "A_A") (pintype "passive"))
      (node (ref "C5") (pin "1") (pinfunction "1_1") (pintype "passive"))
      (node (ref "R5") (pin "1") (pinfunction "1_1") (pintype "passive"))
    )
    (net (code "23") (name "Net-(C11-Pad1)") (class "Default")
      (node (ref "C11") (pin "1") (pinfunction "1_1") (pintype "passive"))
      (node (ref "R4") (pin "2") (pinfunction "2_2") (pintype "passive"))
    )
    (net (code "24") (name "Net-(D1-PadA)") (class "Default")
      (node (ref "D1") (pin "A") (pinfunction "A_A") (pintype "passive"))
      (node (ref "S2") (pin "P$1") (pinfunction "1_P$1") (pintype "passive"))
      (node (ref "S2") (pin "P$2") (pinfunction "1_P$2") (pintype "passive"))
    )
    (net (code "25") (name "Net-(D2-PadA)") (class "Default")
      (node (ref "D2") (pin "A") (pinfunction "A_A") (pintype "passive"))
      (node (ref "S3") (pin "P$1") (pinfunction "1_P$1") (pintype "passive"))
      (node (ref "S3") (pin "P$2") (pinfunction "1_P$2") (pintype "passive"))
    )
    (net (code "26") (name "Net-(D3-PadA)") (class "Default")
      (node (ref "D3") (pin "A") (pinfunction "A_A") (pintype "passive"))
      (node (ref "S4") (pin "P$1") (pinfunction "1_P$1") (pintype "passive"))
      (node (ref "S4") (pin "P$2") (pinfunction "1_P$2") (pintype "passive"))
    )
    (net (code "27") (name "Net-(D4-PadA)") (class "Default")
      (node (ref "D4") (pin "A") (pinfunction "A_A") (pintype "passive"))
      (node (ref "S5") (pin "P$1") (pinfunction "1_P$1") (pintype "passive"))
      (node (ref "S5") (pin "P$2") (pinfunction "1_P$2") (pintype "passive"))
    )
    (net (code "28") (name "Net-(D5-PadA)") (class "Default")
      (node (ref "D5") (pin "A") (pinfunction "A_A") (pintype "passive"))
      (node (ref "S6") (pin "P$1") (pinfunction "1_P$1") (pintype "passive"))
      (node (ref "S6") (pin "P$2") (pinfunction "1_P$2") (pintype "passive"))
    )
    (net (code "29") (name "Net-(D6-PadA)") (class "Default")
      (node (ref "D6") (pin "A") (pinfunction "A_A") (pintype "passive"))
      (node (ref "S7") (pin "P$1") (pinfunction "1_P$1") (pintype "passive"))
      (node (ref "S7") (pin "P$2") (pinfunction "1_P$2") (pintype "passive"))
    )
    (net (code "30") (name "Net-(D7-PadA)") (class "Default")
      (node (ref "D7") (pin "A") (pinfunction "A_A") (pintype "passive"))
      (node (ref "S8") (pin "P$1") (pinfunction "1_P$1") (pintype "passive"))
      (node (ref "S8") (pin "P$2") (pinfunction "1_P$2") (pintype "passive"))
    )
    (net (code "31") (name "Net-(D8-PadA)") (class "Default")
      (node (ref "D8") (pin "A") (pinfunction "A_A") (pintype "passive"))
      (node (ref "S9") (pin "P$1") (pinfunction "1_P$1") (pintype "passive"))
      (node (ref "S9") (pin "P$2") (pinfunction "1_P$2") (pintype "passive"))
    )
    (net (code "32") (name "Net-(D9-PadA)") (class "Default")
      (node (ref "D9") (pin "A") (pinfunction "A_A") (pintype "passive"))
      (node (ref "S10") (pin "P$1") (pinfunction "1_P$1") (pintype "passive"))
      (node (ref "S10") (pin "P$2") (pinfunction "1_P$2") (pintype "passive"))
    )
    (net (code "33") (name "Net-(D10-PadA)") (class "Default")
      (node (ref "D10") (pin "A") (pinfunction "A_A") (pintype "passive"))
      (node (ref "S11") (pin "P$1") (pinfunction "1_P$1") (pintype "passive"))
      (node (ref "S11") (pin "P$2") (pinfunction "1_P$2") (pintype "passive"))
    )
    (net (code "34") (name "Net-(D11-PadA)") (class "Default")
      (node (ref "D11") (pin "A") (pinfunction "A_A") (pintype "passive"))
      (node (ref "S12") (pin "P$1") (pinfunction "1_P$1") (pintype "passive"))
      (node (ref "S12") (pin "P$2") (pinfunction "1_P$2") (pintype "passive"))
    )
    (net (code "35") (name "Net-(D12-PadA)") (class "Default")
      (node (ref "D12") (pin "A") (pinfunction "A_A") (pintype "passive"))
      (node (ref "S13") (pin "P$1") (pinfunction "1_P$1") (pintype "passive"))
      (node (ref "S13") (pin "P$2") (pinfunction "1_P$2") (pintype "passive"))
    )
    (net (code "36") (name "Net-(D13-PadA)") (class "Default")
      (node (ref "D13") (pin "A") (pinfunction "A_A") (pintype "passive"))
      (node (ref "S14") (pin "P$1") (pinfunction "1_P$1") (pintype "passive"))
      (node (ref "S14") (pin "P$2") (pinfunction "1_P$2") (pintype "passive"))
    )
    (net (code "37") (name "Net-(D14-PadA)") (class "Default")
      (node (ref "D14") (pin "A") (pinfunction "A_A") (pintype "passive"))
      (node (ref "S15") (pin "P$1") (pinfunction "1_P$1") (pintype "passive"))
      (node (ref "S15") (pin "P$2") (pinfunction "1_P$2") (pintype "passive"))
    )
    (net (code "38") (name "Net-(D15-PadA)") (class "Default")
      (node (ref "D15") (pin "A") (pinfunction "A_A") (pintype "passive"))
      (node (ref "S16") (pin "P$1") (pinfunction "1_P$1") (pintype "passive"))
      (node (ref "S16") (pin "P$2") (pinfunction "1_P$2") (pintype "passive"))
    )
    (net (code "39") (name "Net-(D16-PadA)") (class "Default")
      (node (ref "D16") (pin "A") (pinfunction "A_A") (pintype "passive"))
      (node (ref "RUN") (pin "P$1") (pinfunction "1_P$1") (pintype "passive"))
      (node (ref "RUN") (pin "P$2") (pinfunction "1_P$2") (pintype "passive"))
    )
    (net (code "40") (name "Net-(D17-PadA)") (class "Default")
      (node (ref "D17") (pin "A") (pinfunction "A_A") (pintype "passive"))
      (node (ref "REPEAT") (pin "P$1") (pinfunction "1_P$1") (pintype "passive"))
      (node (ref "REPEAT") (pin "P$2") (pinfunction "1_P$2") (pintype "passive"))
    )
    (net (code "41") (name "Net-(D18-PadA)") (class "Default")
      (node (ref "D18") (pin "A") (pinfunction "A_A") (pintype "passive"))
      (node (ref "MENU") (pin "P$1") (pinfunction "1_P$1") (pintype "passive"))
      (node (ref "MENU") (pin "P$2") (pinfunction "1_P$2") (pintype "passive"))
    )
    (net (code "42") (name "Net-(D25-PadA)") (class "Default")
      (node (ref "D25") (pin "A") (pinfunction "A_A") (pintype "passive"))
      (node (ref "S1") (pin "P$1") (pinfunction "1_P$1") (pintype "passive"))
      (node (ref "S1") (pin "P$2") (pinfunction "1_P$2") (pintype "passive"))
    )
    (net (code "43") (name "Net-(JP1-Pad2)") (class "Default")
      (node (ref "JP1") (pin "2") (pinfunction "2_2") (pintype "passive"))
      (node (ref "R5") (pin "2") (pinfunction "2_2") (pintype "passive"))
    )
    (net (code "44") (name "Net-(LCD-~{RST})") (class "Default")
      (node (ref "C1") (pin "1") (pinfunction "1_1") (pintype "passive"))
      (node (ref "LCD") (pin "4") (pinfunction "~{RST}_4") (pintype "input"))
      (node (ref "R2") (pin "1") (pinfunction "1_1") (pintype "passive"))
    )
    (net (code "45") (name "Net-(MAX6957-ISET)") (class "Default")
      (node (ref "MAX6957") (pin "1") (pinfunction "ISET_1") (pintype "passive"))
      (node (ref "R1") (pin "2") (pinfunction "2_2") (pintype "passive"))
    )
    (net (code "46") (name "Net-(MAX6957-P12)") (class "Default")
      (node (ref "LED1") (pin "C") (pinfunction "C_C") (pintype "passive"))
      (node (ref "MAX6957") (pin "5") (pinfunction "P12_5") (pintype "bidirectional"))
    )
    (net (code "47") (name "Net-(MAX6957-P13)") (class "Default")
      (node (ref "LED2") (pin "C") (pinfunction "C_C") (pintype "passive"))
      (node (ref "MAX6957") (pin "6") (pinfunction "P13_6") (pintype "bidirectional"))
    )
    (net (code "48") (name "Net-(MAX6957-P14)") (class "Default")
      (node (ref "LED3") (pin "C") (pinfunction "C_C") (pintype "passive"))
      (node (ref "MAX6957") (pin "7") (pinfunction "P14_7") (pintype "bidirectional"))
    )
    (net (code "49") (name "Net-(MAX6957-P16)") (class "Default")
      (node (ref "LED9") (pin "C") (pinfunction "C_C") (pintype "passive"))
      (node (ref "MAX6957") (pin "9") (pinfunction "P16_9") (pintype "bidirectional"))
    )
    (net (code "50") (name "Net-(MAX6957-P17)") (class "Default")
      (node (ref "LED10") (pin "C") (pinfunction "C_C") (pintype "passive"))
      (node (ref "MAX6957") (pin "10") (pinfunction "P17_10") (pintype "bidirectional"))
    )
    (net (code "51") (name "Net-(MAX6957-P18)") (class "Default")
      (node (ref "LED11") (pin "C") (pinfunction "C_C") (pintype "passive"))
      (node (ref "MAX6957") (pin "11") (pinfunction "P18_11") (pintype "bidirectional"))
    )
    (net (code "52") (name "Net-(MAX6957-P19)") (class "Default")
      (node (ref "LED13") (pin "C") (pinfunction "C_C") (pintype "passive"))
      (node (ref "MAX6957") (pin "12") (pinfunction "P19_12") (pintype "bidirectional"))
    )
    (net (code "53") (name "Net-(MAX6957-P20)") (class "Default")
      (node (ref "LED12") (pin "C") (pinfunction "C_C") (pintype "passive"))
      (node (ref "MAX6957") (pin "13") (pinfunction "P20_13") (pintype "bidirectional"))
    )
    (net (code "54") (name "Net-(MAX6957-P21)") (class "Default")
      (node (ref "LED4") (pin "C") (pinfunction "C_C") (pintype "passive"))
      (node (ref "MAX6957") (pin "14") (pinfunction "P21_14") (pintype "bidirectional"))
    )
    (net (code "55") (name "Net-(MAX6957-P22)") (class "Default")
      (node (ref "LED5") (pin "C") (pinfunction "C_C") (pintype "passive"))
      (node (ref "MAX6957") (pin "15") (pinfunction "P22_15") (pintype "bidirectional"))
    )
    (net (code "56") (name "Net-(MAX6957-P23)") (class "Default")
      (node (ref "LED14") (pin "C") (pinfunction "C_C") (pintype "passive"))
      (node (ref "MAX6957") (pin "16") (pinfunction "P23_16") (pintype "bidirectional"))
    )
    (net (code "57") (name "Net-(MAX6957-P24)") (class "Default")
      (node (ref "LED15") (pin "C") (pinfunction "C_C") (pintype "passive"))
      (node (ref "MAX6957") (pin "17") (pinfunction "P24_17") (pintype "bidirectional"))
    )
    (net (code "58") (name "Net-(MAX6957-P25)") (class "Default")
      (node (ref "LED16") (pin "C") (pinfunction "C_C") (pintype "passive"))
      (node (ref "MAX6957") (pin "18") (pinfunction "P25_18") (pintype "bidirectional"))
    )
    (net (code "59") (name "Net-(MAX6957-P26)") (class "Default")
      (node (ref "LED_RUN") (pin "C") (pinfunction "C_C") (pintype "passive"))
      (node (ref "MAX6957") (pin "19") (pinfunction "P26_19") (pintype "bidirectional"))
    )
    (net (code "60") (name "Net-(MAX6957-P27)") (class "Default")
      (node (ref "LED6") (pin "C") (pinfunction "C_C") (pintype "passive"))
      (node (ref "MAX6957") (pin "20") (pinfunction "P27_20") (pintype "bidirectional"))
    )
    (net (code "61") (name "Net-(MAX6957-P28)") (class "Default")
      (node (ref "LED_REPEAT") (pin "C") (pinfunction "C_C") (pintype "passive"))
      (node (ref "MAX6957") (pin "21") (pinfunction "P28_21") (pintype "bidirectional"))
    )
    (net (code "62") (name "Net-(MAX6957-P29)") (class "Default")
      (node (ref "LED7") (pin "C") (pinfunction "C_C") (pintype "passive"))
      (node (ref "MAX6957") (pin "22") (pinfunction "P29_22") (pintype "bidirectional"))
    )
    (net (code "63") (name "Net-(MAX6957-P30)") (class "Default")
      (node (ref "LED_MENU") (pin "C") (pinfunction "C_C") (pintype "passive"))
      (node (ref "MAX6957") (pin "23") (pinfunction "P30_23") (pintype "bidirectional"))
    )
    (net (code "64") (name "Net-(MAX6957-P31)") (class "Default")
      (node (ref "LED8") (pin "C") (pinfunction "C_C") (pintype "passive"))
      (node (ref "MAX6957") (pin "24") (pinfunction "P31_24") (pintype "bidirectional"))
    )
    (net (code "65") (name "Net-(PIC32MX-RB0)") (class "Default")
      (node (ref "MENU") (pin "P$3") (pinfunction "2_P$3") (pintype "passive"))
      (node (ref "MENU") (pin "P$4") (pinfunction "2_P$4") (pintype "passive"))
      (node (ref "PIC32MX") (pin "4") (pinfunction "RB0_4") (pintype "bidirectional"))
      (node (ref "S1") (pin "P$3") (pinfunction "2_P$3") (pintype "passive"))
      (node (ref "S1") (pin "P$4") (pinfunction "2_P$4") (pintype "passive"))
      (node (ref "S9") (pin "P$3") (pinfunction "2_P$3") (pintype "passive"))
      (node (ref "S9") (pin "P$4") (pinfunction "2_P$4") (pintype "passive"))
    )
    (net (code "66") (name "Net-(PIC32MX-RB1)") (class "Default")
      (node (ref "PIC32MX") (pin "5") (pinfunction "RB1_5") (pintype "bidirectional"))
      (node (ref "REPEAT") (pin "P$3") (pinfunction "2_P$3") (pintype "passive"))
      (node (ref "REPEAT") (pin "P$4") (pinfunction "2_P$4") (pintype "passive"))
      (node (ref "S10") (pin "P$3") (pinfunction "2_P$3") (pintype "passive"))
      (node (ref "S10") (pin "P$4") (pinfunction "2_P$4") (pintype "passive"))
      (node (ref "S2") (pin "P$3") (pinfunction "2_P$3") (pintype "passive"))
      (node (ref "S2") (pin "P$4") (pinfunction "2_P$4") (pintype "passive"))
    )
    (net (code "67") (name "Net-(PIC32MX-RB2)") (class "Default")
      (node (ref "PIC32MX") (pin "6") (pinfunction "RB2_6") (pintype "bidirectional"))
      (node (ref "RUN") (pin "P$3") (pinfunction "2_P$3") (pintype "passive"))
      (node (ref "RUN") (pin "P$4") (pinfunction "2_P$4") (pintype "passive"))
      (node (ref "S11") (pin "P$3") (pinfunction "2_P$3") (pintype "passive"))
      (node (ref "S11") (pin "P$4") (pinfunction "2_P$4") (pintype "passive"))
      (node (ref "S3") (pin "P$3") (pinfunction "2_P$3") (pintype "passive"))
      (node (ref "S3") (pin "P$4") (pinfunction "2_P$4") (pintype "passive"))
    )
    (net (code "68") (name "Net-(PIC32MX-RB3)") (class "Default")
      (node (ref "D19") (pin "A") (pinfunction "A_A") (pintype "passive"))
      (node (ref "PIC32MX") (pin "7") (pinfunction "RB3_7") (pintype "bidirectional"))
      (node (ref "S12") (pin "P$3") (pinfunction "2_P$3") (pintype "passive"))
      (node (ref "S12") (pin "P$4") (pinfunction "2_P$4") (pintype "passive"))
      (node (ref "S4") (pin "P$3") (pinfunction "2_P$3") (pintype "passive"))
      (node (ref "S4") (pin "P$4") (pinfunction "2_P$4") (pintype "passive"))
    )
    (net (code "69") (name "Net-(PIC32MX-RB4)") (class "Default")
      (node (ref "D20") (pin "A") (pinfunction "A_A") (pintype "passive"))
      (node (ref "PIC32MX") (pin "11") (pinfunction "RB4_11") (pintype "bidirectional"))
      (node (ref "S13") (pin "P$3") (pinfunction "2_P$3") (pintype "passive"))
      (node (ref "S13") (pin "P$4") (pinfunction "2_P$4") (pintype "passive"))
      (node (ref "S5") (pin "P$3") (pinfunction "2_P$3") (pintype "passive"))
      (node (ref "S5") (pin "P$4") (pinfunction "2_P$4") (pintype "passive"))
    )
    (net (code "70") (name "Net-(PIC32MX-RB5)") (class "Default")
      (node (ref "D21") (pin "A") (pinfunction "A_A") (pintype "passive"))
      (node (ref "PIC32MX") (pin "14") (pinfunction "RB5_14") (pintype "bidirectional"))
      (node (ref "S14") (pin "P$3") (pinfunction "2_P$3") (pintype "passive"))
      (node (ref "S14") (pin "P$4") (pinfunction "2_P$4") (pintype "passive"))
      (node (ref "S6") (pin "P$3") (pinfunction "2_P$3") (pintype "passive"))
      (node (ref "S6") (pin "P$4") (pinfunction "2_P$4") (pintype "passive"))
    )
    (net (code "71") (name "Net-(PIC32MX-RB6)") (class "Default")
      (node (ref "D22") (pin "A") (pinfunction "A_A") (pintype "passive"))
      (node (ref "PIC32MX") (pin "15") (pinfunction "RB6_15") (pintype "bidirectional"))
      (node (ref "S15") (pin "P$3") (pinfunction "2_P$3") (pintype "passive"))
      (node (ref "S15") (pin "P$4") (pinfunction "2_P$4") (pintype "passive"))
      (node (ref "S7") (pin "P$3") (pinfunction "2_P$3") (pintype "passive"))
      (node (ref "S7") (pin "P$4") (pinfunction "2_P$4") (pintype "passive"))
    )
    (net (code "72") (name "Net-(PIC32MX-RB7)") (class "Default")
      (node (ref "D23") (pin "A") (pinfunction "A_A") (pintype "passive"))
      (node (ref "PIC32MX") (pin "16") (pinfunction "RB7_16") (pintype "bidirectional"))
      (node (ref "S16") (pin "P$3") (pinfunction "2_P$3") (pintype "passive"))
      (node (ref "S16") (pin "P$4") (pinfunction "2_P$4") (pintype "passive"))
      (node (ref "S8") (pin "P$3") (pinfunction "2_P$3") (pintype "passive"))
      (node (ref "S8") (pin "P$4") (pinfunction "2_P$4") (pintype "passive"))
    )
    (net (code "73") (name "Net-(PIC32MX-VCAP)") (class "Default")
      (node (ref "C7") (pin "+") (pinfunction "+_+") (pintype "passive"))
      (node (ref "PIC32MX") (pin "20") (pinfunction "VCAP_20") (pintype "passive"))
    )
    (net (code "74") (name "Net-(POWER-O)") (class "Default")
      (node (ref "POWER") (pin "1") (pinfunction "O_1") (pintype "passive"))
      (node (ref "U2") (pin "3") (pinfunction "VIN_3") (pintype "bidirectional"))
    )
    (net (code "75") (name "Net-(S18-A)") (class "Default")
      (node (ref "D19") (pin "C") (pinfunction "C_C") (pintype "passive"))
      (node (ref "S18") (pin "1") (pinfunction "A_1") (pintype "passive"))
    )
    (net (code "76") (name "Net-(S18-B)") (class "Default")
      (node (ref "D20") (pin "C") (pinfunction "C_C") (pintype "passive"))
      (node (ref "S18") (pin "2") (pinfunction "B_2") (pintype "passive"))
    )
    (net (code "77") (name "Net-(S18-C)") (class "Default")
      (node (ref "D21") (pin "C") (pinfunction "C_C") (pintype "passive"))
      (node (ref "S18") (pin "3") (pinfunction "C_3") (pintype "passive"))
    )
    (net (code "78") (name "Net-(S18-D)") (class "Default")
      (node (ref "D22") (pin "C") (pinfunction "C_C") (pintype "passive"))
      (node (ref "S18") (pin "5") (pinfunction "D_5") (pintype "passive"))
    )
    (net (code "79") (name "Net-(S18-PUSH)") (class "Default")
      (node (ref "D23") (pin "C") (pinfunction "C_C") (pintype "passive"))
      (node (ref "S18") (pin "6") (pinfunction "PUSH_6") (pintype "passive"))
    )
    (net (code "80") (name "Net-(TF-DAT1_N{slash}C)") (class "Default")
      (node (ref "R13") (pin "1") (pinfunction "1_1") (pintype "passive"))
      (node (ref "TF") (pin "8") (pinfunction "DAT1_N/C_8") (pintype "bidirectional"))
    )
    (net (code "81") (name "Net-(TF-DAT2_N{slash}C)") (class "Default")
      (node (ref "R12") (pin "1") (pinfunction "1_1") (pintype "passive"))
      (node (ref "TF") (pin "1") (pinfunction "DAT2_N/C_1") (pintype "bidirectional"))
    )
    (net (code "82") (name "Net-(TPA301-BYPASS)") (class "Default")
      (node (ref "C2") (pin "1") (pinfunction "1_1") (pintype "passive"))
      (node (ref "TPA301") (pin "2") (pinfunction "BYPASS_2") (pintype "input"))
      (node (ref "TPA301") (pin "3") (pinfunction "IN+_3") (pintype "input"))
    )
    (net (code "83") (name "Net-(TPA301-IN-)") (class "Default")
      (node (ref "GAIN") (pin "A") (pinfunction "A_A") (pintype "passive"))
      (node (ref "R4") (pin "1") (pinfunction "1_1") (pintype "passive"))
      (node (ref "TPA301") (pin "4") (pinfunction "IN-_4") (pintype "input"))
    )
    (net (code "84") (name "Net-(TPA301-VO+)") (class "Default")
      (node (ref "GAIN") (pin "E") (pinfunction "E_E") (pintype "passive"))
      (node (ref "GAIN") (pin "S") (pinfunction "S_S") (pintype "passive"))
      (node (ref "SPEAKER") (pin "1") (pinfunction "1_1") (pintype "passive"))
      (node (ref "TPA301") (pin "5") (pinfunction "VO+_5") (pintype "output"))
    )
    (net (code "85") (name "Net-(TPA301-VO-)") (class "Default")
      (node (ref "SPEAKER") (pin "2") (pinfunction "2_2") (pintype "passive"))
      (node (ref "TPA301") (pin "8") (pinfunction "VO-_8") (pintype "output"))
    )
    (net (code "86") (name "Net-(U3-RIGHT)") (class "Default")
      (node (ref "C6") (pin "-") (pinfunction "-_-") (pintype "passive"))
      (node (ref "U3") (pin "L") (pinfunction "LEFT_L") (pintype "bidirectional"))
      (node (ref "U3") (pin "L@1") (pinfunction "LEFT_L@1") (pintype "bidirectional"))
      (node (ref "U3") (pin "R") (pinfunction "RIGHT_R") (pintype "bidirectional"))
    )
    (net (code "87") (name "unconnected-(MAX6957-DOUT-Pad4)") (class "Default")
      (node (ref "MAX6957") (pin "4") (pinfunction "DOUT_4") (pintype "bidirectional"))
    )
    (net (code "88") (name "unconnected-(POWER-S-Pad3)") (class "Default")
      (node (ref "POWER") (pin "3") (pinfunction "S_3") (pintype "passive"))
    )
    (net (code "89") (name "unconnected-(TF-PadCD1)") (class "Default")
      (node (ref "TF") (pin "CD1") (pinfunction "CD1_CD1") (pintype "open_collector"))
    )
    (net (code "90") (name "unconnected-(TF-PadCD2)") (class "Default")
      (node (ref "TF") (pin "CD2") (pinfunction "CD2_CD2") (pintype "open_collector"))
    )
  )
)
